# DenScript_LED_V1_0.net
KiCad netlist of a schematic drawn in EAGLE
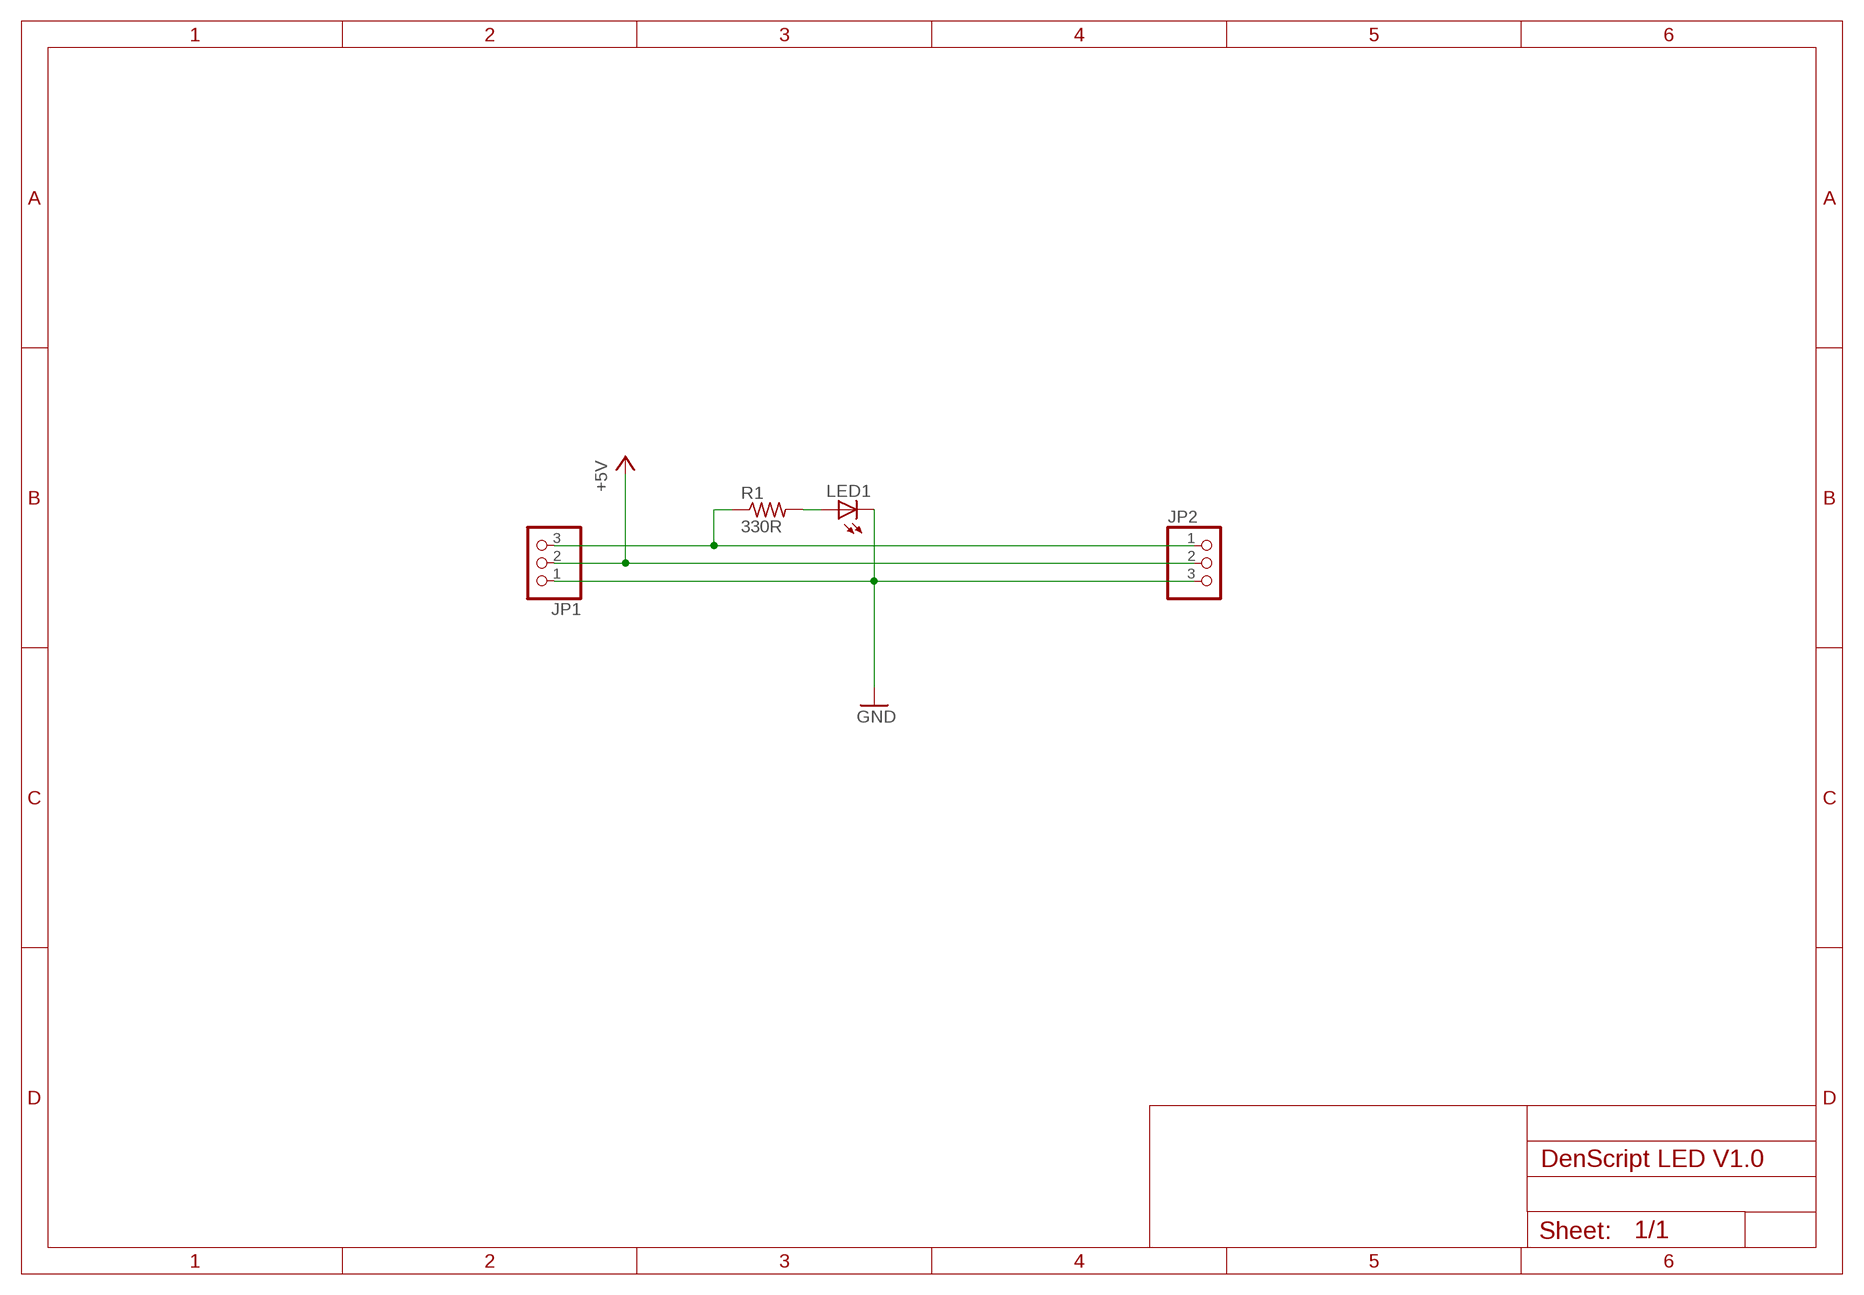
[diagram p0: schematic, sheet 1]

(export (version "E")
  (design (tool "Eeschema 10.0.6"))
  (components
    (comp (ref "JP1")
      (value "PINHD-1X3")
      (footprint "eagle-import:1X03")
      (libsource (lib "eagle-import") (part "PINHD-1X3"))
    )
    (comp (ref "JP2")
      (value "PINHD-1X3")
      (footprint "eagle-import:1X03")
      (libsource (lib "eagle-import") (part "PINHD-1X3"))
    )
    (comp (ref "LED1")
      (value "LED5MM")
      (footprint "eagle-import:LED5MM")
      (libsource (lib "eagle-import") (part "LED5MM"))
    )
    (comp (ref "R1")
      (value "330R")
      (footprint "eagle-import:R0603")
      (libsource (lib "eagle-import") (part "R-US_R0603"))
    )
  )
  (nets
    (net (code "1") (name "+5V") (class "Default")
      (node (ref "JP1") (pin "2") (pinfunction "2_2") (pintype "passive"))
      (node (ref "JP2") (pin "2") (pinfunction "2_2") (pintype "passive"))
    )
    (net (code "2") (name "GND") (class "Default")
      (node (ref "JP1") (pin "1") (pinfunction "1_1") (pintype "passive"))
      (node (ref "JP2") (pin "3") (pinfunction "3_3") (pintype "passive"))
      (node (ref "LED1") (pin "K") (pinfunction "C_K") (pintype "passive"))
    )
    (net (code "3") (name "Net-(JP1-Pad3)") (class "Default")
      (node (ref "JP1") (pin "3") (pinfunction "3_3") (pintype "passive"))
      (node (ref "JP2") (pin "1") (pinfunction "1_1") (pintype "passive"))
      (node (ref "R1") (pin "1") (pinfunction "1_1") (pintype "passive"))
    )
    (net (code "4") (name "Net-(LED1-PadA)") (class "Default")
      (node (ref "LED1") (pin "A") (pinfunction "A_A") (pintype "passive"))
      (node (ref "R1") (pin "2") (pinfunction "2_2") (pintype "passive"))
    )
  )
)
